# Optos.net
KiCad netlist of a schematic drawn in Altium Designer
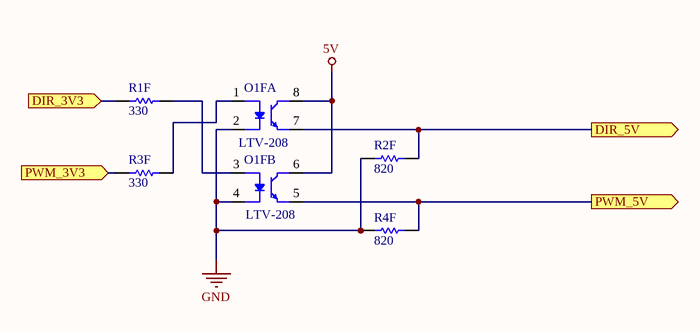
[diagram p0: Optos.SchDoc]

(export (version "E")
  (design (tool "Eeschema 10.0.6"))
  (components
    (comp (ref "O1F")
      (value "LTV-208")
      (footprint "SSOP8 Lite-on")
      (description "2 Channel Optoisolator")
      (fields (field (name "MANUFACTURER PART NUMBER") "LTV-208"))
      (libsource (lib "URC") (part "LTV-208, 3.75KV"))
    )
    (comp (ref "R1F")
      (value "330")
      (footprint "R0603")
      (description "Resistor")
      (fields (field (name "TOLERANCE") "1%") (field (name "MANUFACTURER PART NUMBER") "RC0603JR-07330RL"))
      (libsource (lib "Resistors SchLib") (part "330, 5%, 100mW, Yageo, R0603"))
    )
    (comp (ref "R2F")
      (value "820")
      (footprint "R0603")
      (description "Resistor")
      (fields (field (name "TOLERANCE") "1%") (field (name "MANUFACTURER PART NUMBER") "RC0603JR-07820RL"))
      (libsource (lib "Resistors SchLib") (part "820, 5%, 100mW, Yageo, R0603"))
    )
    (comp (ref "R3F")
      (value "330")
      (footprint "R0603")
      (description "Resistor")
      (fields (field (name "TOLERANCE") "1%") (field (name "MANUFACTURER PART NUMBER") "RC0603JR-07330RL"))
      (libsource (lib "Resistors SchLib") (part "330, 5%, 100mW, Yageo, R0603"))
    )
    (comp (ref "R4F")
      (value "820")
      (footprint "R0603")
      (description "Resistor")
      (fields (field (name "TOLERANCE") "1%") (field (name "MANUFACTURER PART NUMBER") "RC0603JR-07820RL"))
      (libsource (lib "Resistors SchLib") (part "820, 5%, 100mW, Yageo, R0603"))
    )
  )
  (nets
    (net (code "1") (name "/DIR_3V3") (class "Default")
      (node (ref "R1F") (pin "1") (pinfunction "1_1") (pintype "passive"))
    )
    (net (code "2") (name "/DIR_5V") (class "Default")
      (node (ref "O1F") (pin "7") (pinfunction "7_7") (pintype "passive"))
      (node (ref "R2F") (pin "1") (pinfunction "1_1") (pintype "passive"))
    )
    (net (code "3") (name "/PWM_3V3") (class "Default")
      (node (ref "R3F") (pin "1") (pinfunction "1_1") (pintype "passive"))
    )
    (net (code "4") (name "/PWM_5V") (class "Default")
      (node (ref "O1F") (pin "5") (pinfunction "5_5") (pintype "passive"))
      (node (ref "R4F") (pin "1") (pinfunction "1_1") (pintype "passive"))
    )
    (net (code "5") (name "5V") (class "Default")
      (node (ref "O1F") (pin "6") (pinfunction "6_6") (pintype "passive"))
      (node (ref "O1F") (pin "8") (pinfunction "8_8") (pintype "passive"))
    )
    (net (code "6") (name "GND") (class "Default")
      (node (ref "O1F") (pin "2") (pinfunction "2_2") (pintype "passive"))
      (node (ref "O1F") (pin "4") (pinfunction "4_4") (pintype "passive"))
      (node (ref "R2F") (pin "2") (pinfunction "2_2") (pintype "passive"))
      (node (ref "R4F") (pin "2") (pinfunction "2_2") (pintype "passive"))
    )
    (net (code "7") (name "Net-(O1F-Pad1)") (class "Default")
      (node (ref "O1F") (pin "1") (pinfunction "1_1") (pintype "passive"))
      (node (ref "R3F") (pin "2") (pinfunction "2_2") (pintype "passive"))
    )
    (net (code "8") (name "Net-(O1F-Pad3)") (class "Default")
      (node (ref "O1F") (pin "3") (pinfunction "3_3") (pintype "passive"))
      (node (ref "R1F") (pin "2") (pinfunction "2_2") (pintype "passive"))
    )
  )
)
